# eggfckr.net
KiCad netlist of a schematic drawn in EAGLE
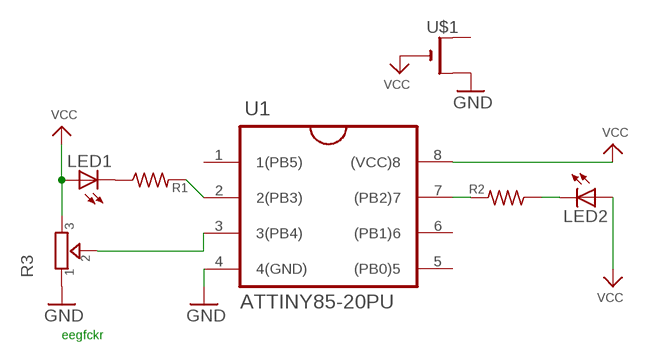
[diagram p0: schematic, sheet 1]

(export (version "E")
  (design (tool "Eeschema 10.0.6"))
  (components
    (comp (ref "LED1")
      (value "LED3MM")
      (footprint "eagle-import:LED3MM")
      (libsource (lib "eagle-import") (part "LED3MM"))
    )
    (comp (ref "LED2")
      (value "LED3MM")
      (footprint "eagle-import:LED3MM")
      (libsource (lib "eagle-import") (part "LED3MM"))
    )
    (comp (ref "R1")
      (value "R-US_0204/7")
      (footprint "eagle-import:0204_7")
      (libsource (lib "eagle-import") (part "R-US_0204/7"))
    )
    (comp (ref "R2")
      (value "R-US_0204/7")
      (footprint "eagle-import:0204_7")
      (libsource (lib "eagle-import") (part "R-US_0204/7"))
    )
    (comp (ref "R3")
      (value "TRIMMER-3306F")
      (footprint "eagle-import:TRIMMER_3306F")
      (libsource (lib "eagle-import") (part "TRIMMER-3306F"))
    )
    (comp (ref "U$1")
      (value "CR2032THM")
      (footprint "eagle-import:CR2032-THRU")
      (libsource (lib "eagle-import") (part "CR2032THM"))
    )
    (comp (ref "U1")
      (value "ATTINY85-20PU")
      (footprint "eagle-import:DIP254P762X533-8")
      (libsource (lib "eagle-import") (part "ATTINY85-20PU"))
    )
  )
  (nets
    (net (code "1") (name "GND") (class "Default")
      (node (ref "R3") (pin "1") (pinfunction "1_1") (pintype "passive"))
      (node (ref "U$1") (pin "+2") (pinfunction "+1_+2") (pintype "passive"))
      (node (ref "U1") (pin "4") (pinfunction "4(GND)_4") (pintype "passive"))
    )
    (net (code "2") (name "Net-(LED1-C)") (class "Default")
      (node (ref "LED1") (pin "K") (pinfunction "C_K") (pintype "passive"))
      (node (ref "R1") (pin "1") (pinfunction "1_1") (pintype "passive"))
    )
    (net (code "3") (name "Net-(LED2-C)") (class "Default")
      (node (ref "LED2") (pin "K") (pinfunction "C_K") (pintype "passive"))
      (node (ref "R2") (pin "1") (pinfunction "1_1") (pintype "passive"))
    )
    (net (code "4") (name "Net-(U1-(PB2)7)") (class "Default")
      (node (ref "R2") (pin "2") (pinfunction "2_2") (pintype "passive"))
      (node (ref "U1") (pin "7") (pinfunction "(PB2)7_7") (pintype "bidirectional"))
    )
    (net (code "5") (name "Net-(U1-2(PB3))") (class "Default")
      (node (ref "R1") (pin "2") (pinfunction "2_2") (pintype "passive"))
      (node (ref "U1") (pin "2") (pinfunction "2(PB3)_2") (pintype "bidirectional"))
    )
    (net (code "6") (name "Net-(U1-3(PB4))") (class "Default")
      (node (ref "R3") (pin "2") (pinfunction "2_2") (pintype "passive"))
      (node (ref "U1") (pin "3") (pinfunction "3(PB4)_3") (pintype "bidirectional"))
    )
    (net (code "7") (name "VCC") (class "Default")
      (node (ref "LED1") (pin "A") (pinfunction "A_A") (pintype "passive"))
      (node (ref "LED2") (pin "A") (pinfunction "A_A") (pintype "passive"))
      (node (ref "R3") (pin "3") (pinfunction "3_3") (pintype "passive"))
      (node (ref "U$1") (pin "-") (pinfunction "-_-") (pintype "passive"))
      (node (ref "U1") (pin "8") (pinfunction "(VCC)8_8") (pintype "power_in"))
    )
    (net (code "8") (name "unconnected-(U$1-+-Pad+1)") (class "Default")
      (node (ref "U$1") (pin "+1") (pinfunction "+_+1") (pintype "passive"))
    )
    (net (code "9") (name "unconnected-(U1-(PB0)5-Pad5)") (class "Default")
      (node (ref "U1") (pin "5") (pinfunction "(PB0)5_5") (pintype "bidirectional"))
    )
    (net (code "10") (name "unconnected-(U1-(PB1)6-Pad6)") (class "Default")
      (node (ref "U1") (pin "6") (pinfunction "(PB1)6_6") (pintype "bidirectional"))
    )
    (net (code "11") (name "unconnected-(U1-1(PB5)-Pad1)") (class "Default")
      (node (ref "U1") (pin "1") (pinfunction "1(PB5)_1") (pintype "bidirectional"))
    )
  )
)
